# FTDI.net
KiCad netlist of a schematic drawn in EAGLE
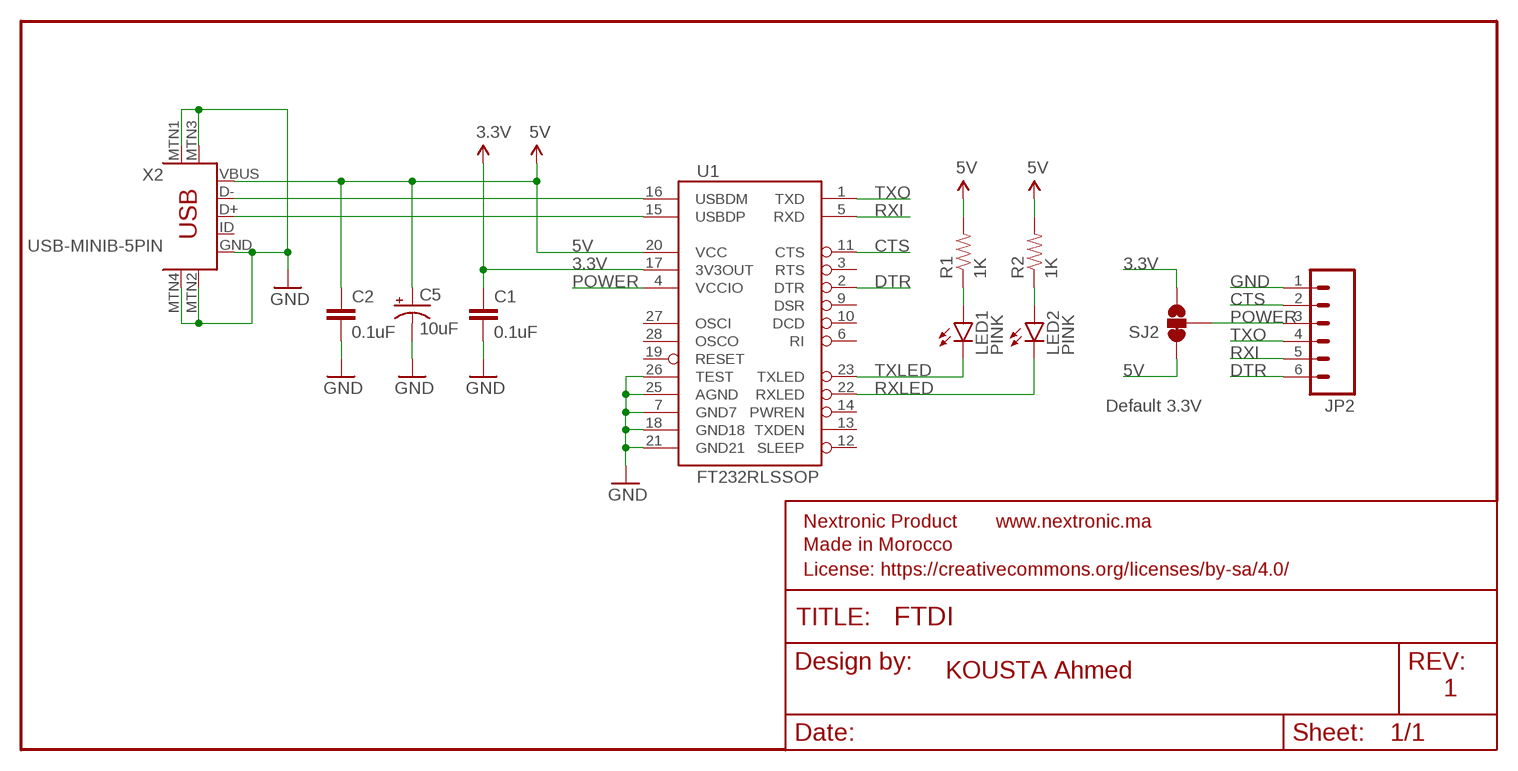
[diagram p0: schematic, sheet 1]

(export (version "E")
  (design (tool "Eeschema 10.0.6"))
  (components
    (comp (ref "C1")
      (value "0.1uF")
      (footprint "eagle-import:0603-CAP")
      (libsource (lib "eagle-import") (part "0.1UF-25V-5%(0603)"))
    )
    (comp (ref "C2")
      (value "0.1uF")
      (footprint "eagle-import:0603-CAP")
      (libsource (lib "eagle-import") (part "0.1UF-25V-5%(0603)"))
    )
    (comp (ref "C5")
      (value "10uF")
      (footprint "eagle-import:EIA3216")
      (libsource (lib "eagle-import") (part "CAP_POL1206"))
    )
    (comp (ref "FRAME2")
      (value "FRAME-LETTER")
      (footprint "eagle-import:CREATIVE_COMMONS")
      (libsource (lib "eagle-import") (part "FRAME-LETTER"))
    )
    (comp (ref "JP2")
      (value "M06SILK_FEMALE_PTH")
      (footprint "eagle-import:1X06")
      (libsource (lib "eagle-import") (part "M06SILK_FEMALE_PTH"))
    )
    (comp (ref "LED1")
      (value "PINK")
      (footprint "eagle-import:LED-1206")
      (libsource (lib "eagle-import") (part "LED-PINK1206"))
    )
    (comp (ref "LED2")
      (value "PINK")
      (footprint "eagle-import:LED-1206")
      (libsource (lib "eagle-import") (part "LED-PINK1206"))
    )
    (comp (ref "R1")
      (value "1K")
      (footprint "eagle-import:0603-RES")
      (libsource (lib "eagle-import") (part "1KOHM-1/10W-1%(0603)"))
    )
    (comp (ref "R2")
      (value "1K")
      (footprint "eagle-import:0603-RES")
      (libsource (lib "eagle-import") (part "1KOHM-1/10W-1%(0603)"))
    )
    (comp (ref "SJ2")
      (value "SOLDERJUMPER_2WAYS")
      (footprint "eagle-import:SJ_3")
      (libsource (lib "eagle-import") (part "SOLDERJUMPER_2WAYS"))
    )
    (comp (ref "U1")
      (value "FT232RLSSOP")
      (footprint "eagle-import:SSOP28DB")
      (libsource (lib "eagle-import") (part "FT232RLSSOP"))
    )
    (comp (ref "X2")
      (value "USB-MINIB-5PIN")
      (footprint "eagle-import:USB-MINIB")
      (libsource (lib "eagle-import") (part "USB-MINIB-5PIN"))
    )
  )
  (nets
    (net (code "1") (name "/CTS") (class "Default")
      (node (ref "JP2") (pin "2") (pinfunction "2_2") (pintype "passive"))
      (node (ref "U1") (pin "11") (pinfunction "CTS_11") (pintype "input"))
    )
    (net (code "2") (name "/DTR") (class "Default")
      (node (ref "JP2") (pin "6") (pinfunction "6_6") (pintype "passive"))
      (node (ref "U1") (pin "2") (pinfunction "DTR_2") (pintype "output"))
    )
    (net (code "3") (name "/POWER") (class "Default")
      (node (ref "JP2") (pin "3") (pinfunction "3_3") (pintype "passive"))
      (node (ref "SJ2") (pin "2") (pinfunction "2_2") (pintype "passive"))
      (node (ref "U1") (pin "4") (pinfunction "VCCIO_4") (pintype "power_in"))
    )
    (net (code "4") (name "/RXI") (class "Default")
      (node (ref "JP2") (pin "5") (pinfunction "5_5") (pintype "passive"))
      (node (ref "U1") (pin "5") (pinfunction "RXD_5") (pintype "input"))
    )
    (net (code "5") (name "/RXLED") (class "Default")
      (node (ref "LED2") (pin "C") (pinfunction "C_C") (pintype "passive"))
      (node (ref "U1") (pin "22") (pinfunction "RXLED_22") (pintype "input"))
    )
    (net (code "6") (name "/TXLED") (class "Default")
      (node (ref "LED1") (pin "C") (pinfunction "C_C") (pintype "passive"))
      (node (ref "U1") (pin "23") (pinfunction "TXLED_23") (pintype "input"))
    )
    (net (code "7") (name "/TXO") (class "Default")
      (node (ref "JP2") (pin "4") (pinfunction "4_4") (pintype "passive"))
      (node (ref "U1") (pin "1") (pinfunction "TXD_1") (pintype "output"))
    )
    (net (code "8") (name "3.3V") (class "Default")
      (node (ref "C1") (pin "1") (pinfunction "1_1") (pintype "passive"))
      (node (ref "SJ2") (pin "3") (pinfunction "3_3") (pintype "passive"))
      (node (ref "U1") (pin "17") (pinfunction "3V3OUT_17") (pintype "output"))
    )
    (net (code "9") (name "5V") (class "Default")
      (node (ref "C2") (pin "1") (pinfunction "1_1") (pintype "passive"))
      (node (ref "C5") (pin "A") (pinfunction "+_A") (pintype "passive"))
      (node (ref "R1") (pin "2") (pinfunction "2_2") (pintype "passive"))
      (node (ref "R2") (pin "2") (pinfunction "2_2") (pintype "passive"))
      (node (ref "SJ2") (pin "1") (pinfunction "1_1") (pintype "passive"))
      (node (ref "U1") (pin "20") (pinfunction "VCC_20") (pintype "power_in"))
      (node (ref "X2") (pin "VBUS") (pinfunction "VBUS_VBUS") (pintype "bidirectional"))
    )
    (net (code "10") (name "GND") (class "Default")
      (node (ref "C1") (pin "2") (pinfunction "2_2") (pintype "passive"))
      (node (ref "C2") (pin "2") (pinfunction "2_2") (pintype "passive"))
      (node (ref "C5") (pin "C") (pinfunction "-_C") (pintype "passive"))
      (node (ref "JP2") (pin "1") (pinfunction "1_1") (pintype "passive"))
      (node (ref "U1") (pin "18") (pinfunction "GND18_18") (pintype "power_in"))
      (node (ref "U1") (pin "21") (pinfunction "GND21_21") (pintype "power_in"))
      (node (ref "U1") (pin "25") (pinfunction "AGND_25") (pintype "power_in"))
      (node (ref "U1") (pin "26") (pinfunction "TEST_26") (pintype "input"))
      (node (ref "U1") (pin "7") (pinfunction "GND7_7") (pintype "power_in"))
      (node (ref "X2") (pin "GND") (pinfunction "GND_GND") (pintype "bidirectional"))
      (node (ref "X2") (pin "MTN1") (pinfunction "MTN2_MTN1") (pintype "bidirectional"))
      (node (ref "X2") (pin "MTN2") (pinfunction "MTN3_MTN2") (pintype "bidirectional"))
      (node (ref "X2") (pin "MTN3") (pinfunction "MTN1_MTN3") (pintype "bidirectional"))
      (node (ref "X2") (pin "MTN4") (pinfunction "MTN4_MTN4") (pintype "bidirectional"))
    )
    (net (code "11") (name "Net-(LED1-PadA)") (class "Default")
      (node (ref "LED1") (pin "A") (pinfunction "A_A") (pintype "passive"))
      (node (ref "R1") (pin "1") (pinfunction "1_1") (pintype "passive"))
    )
    (net (code "12") (name "Net-(LED2-PadA)") (class "Default")
      (node (ref "LED2") (pin "A") (pinfunction "A_A") (pintype "passive"))
      (node (ref "R2") (pin "1") (pinfunction "1_1") (pintype "passive"))
    )
    (net (code "13") (name "Net-(U1-USBDM)") (class "Default")
      (node (ref "U1") (pin "16") (pinfunction "USBDM_16") (pintype "bidirectional"))
      (node (ref "X2") (pin "D-") (pinfunction "D-_D-") (pintype "bidirectional"))
    )
    (net (code "14") (name "Net-(U1-USBDP)") (class "Default")
      (node (ref "U1") (pin "15") (pinfunction "USBDP_15") (pintype "bidirectional"))
      (node (ref "X2") (pin "D+") (pinfunction "D+_D+") (pintype "bidirectional"))
    )
    (net (code "15") (name "unconnected-(U1-DCD-Pad10)") (class "Default")
      (node (ref "U1") (pin "10") (pinfunction "DCD_10") (pintype "input"))
    )
    (net (code "16") (name "unconnected-(U1-DSR-Pad9)") (class "Default")
      (node (ref "U1") (pin "9") (pinfunction "DSR_9") (pintype "input"))
    )
    (net (code "17") (name "unconnected-(U1-OSCI-Pad27)") (class "Default")
      (node (ref "U1") (pin "27") (pinfunction "OSCI_27") (pintype "input"))
    )
    (net (code "18") (name "unconnected-(U1-OSCO-Pad28)") (class "Default")
      (node (ref "U1") (pin "28") (pinfunction "OSCO_28") (pintype "output"))
    )
    (net (code "19") (name "unconnected-(U1-PWREN-Pad14)") (class "Default")
      (node (ref "U1") (pin "14") (pinfunction "PWREN_14") (pintype "input"))
    )
    (net (code "20") (name "unconnected-(U1-RESET-Pad19)") (class "Default")
      (node (ref "U1") (pin "19") (pinfunction "RESET_19") (pintype "input"))
    )
    (net (code "21") (name "unconnected-(U1-RI-Pad6)") (class "Default")
      (node (ref "U1") (pin "6") (pinfunction "RI_6") (pintype "input"))
    )
    (net (code "22") (name "unconnected-(U1-RTS-Pad3)") (class "Default")
      (node (ref "U1") (pin "3") (pinfunction "RTS_3") (pintype "output"))
    )
    (net (code "23") (name "unconnected-(U1-SLEEP-Pad12)") (class "Default")
      (node (ref "U1") (pin "12") (pinfunction "SLEEP_12") (pintype "input"))
    )
    (net (code "24") (name "unconnected-(U1-TXDEN-Pad13)") (class "Default")
      (node (ref "U1") (pin "13") (pinfunction "TXDEN_13") (pintype "input"))
    )
    (net (code "25") (name "unconnected-(X2-PadID)") (class "Default")
      (node (ref "X2") (pin "ID") (pinfunction "ID_ID") (pintype "bidirectional"))
    )
  )
)
